# RESET.net
KiCad netlist of a schematic drawn in Altium Designer
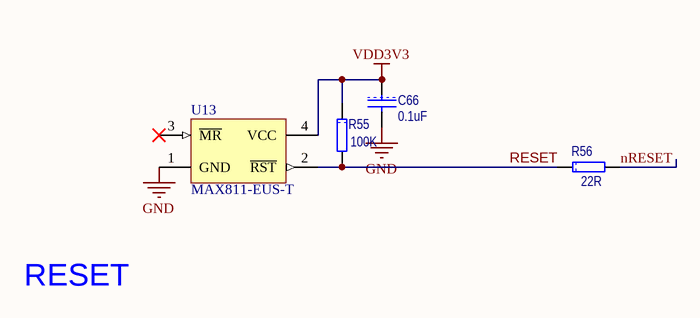
[diagram p0: RESET.SchDoc]

(export (version "E")
  (design (tool "Eeschema 10.0.6"))
  (components
    (comp (ref "C66")
      (value "0.1uF")
      (footprint "1608[0603]")
      (description "Capacitor")
      (fields (field (name "MANUFACTURER") "TDK"))
      (libsource (lib "*") (part "CAP"))
    )
    (comp (ref "R55")
      (value "100K")
      (footprint "1608[0603]R")
      (description "RES")
      (fields (field (name "MANUFACTURER") "vishay"))
      (libsource (lib "*") (part "RES"))
    )
    (comp (ref "R56")
      (value "22R")
      (footprint "1608[0603]R")
      (description "RES")
      (fields (field (name "MANUFACTURER") "vishay"))
      (libsource (lib "*") (part "RES"))
    )
    (comp (ref "U13")
      (value "MAX811-EUS-T")
      (footprint "SOT143_N")
      (description "IC")
      (fields (field (name "PUBLISHER") "Altium Limited"))
      (libsource (lib "Maxim Power Mgt Supervisory Circuit") (part "MAX811-EUS-T"))
    )
  )
  (nets
    (net (code "1") (name "/RESET") (class "Default")
      (node (ref "R55") (pin "2") (pinfunction "2_2") (pintype "passive"))
      (node (ref "R56") (pin "1") (pinfunction "1_1") (pintype "passive"))
      (node (ref "U13") (pin "2") (pinfunction "~{RST}_2") (pintype "output"))
    )
    (net (code "2") (name "/nRESET") (class "Default")
      (node (ref "R56") (pin "2") (pinfunction "2_2") (pintype "passive"))
    )
    (net (code "3") (name "GND") (class "Default")
      (node (ref "C66") (pin "2") (pinfunction "2_2") (pintype "passive"))
      (node (ref "U13") (pin "1") (pinfunction "GND_1") (pintype "power_in"))
    )
    (net (code "4") (name "VDD3V3") (class "Default")
      (node (ref "C66") (pin "1") (pinfunction "1_1") (pintype "passive"))
      (node (ref "R55") (pin "1") (pinfunction "1_1") (pintype "passive"))
      (node (ref "U13") (pin "4") (pinfunction "VCC_4") (pintype "power_in"))
    )
    (net (code "5") (name "unconnected-(U13-~{MR}-Pad3)") (class "Default")
      (node (ref "U13") (pin "3") (pinfunction "~{MR}_3") (pintype "input+no_connect"))
    )
  )
)
